# M215A.net
KiCad netlist of a schematic drawn in EAGLE
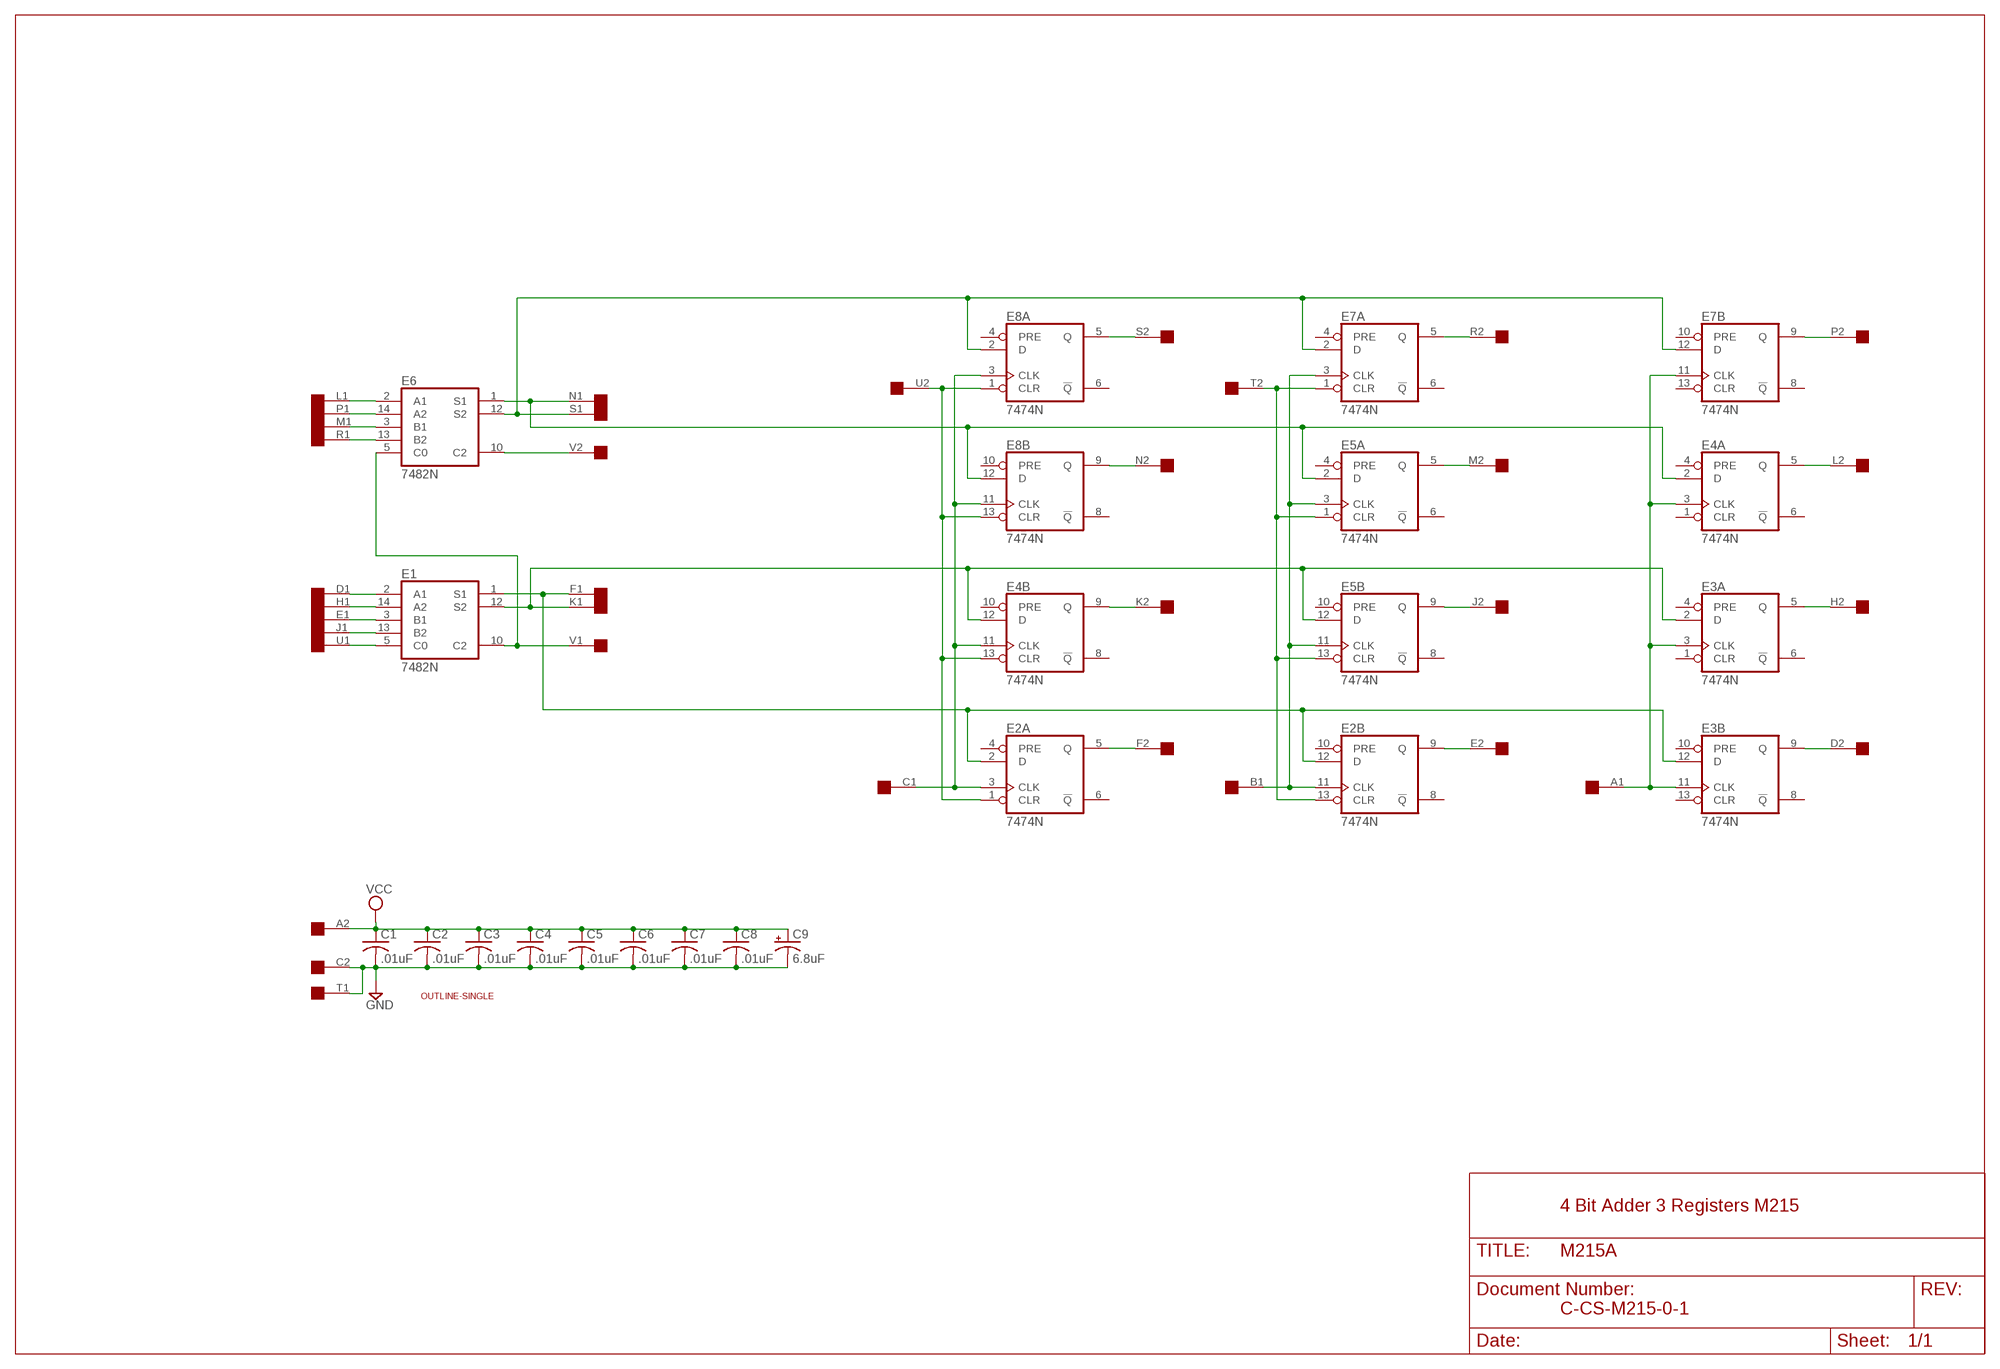
[diagram p0: schematic, sheet 1]

(export (version "E")
  (design (tool "Eeschema 10.0.6"))
  (components
    (comp (ref "C1")
      (value ".01uF")
      (footprint "eagle-import:C050-025X075")
      (libsource (lib "eagle-import") (part "C-US050-025X075"))
    )
    (comp (ref "C2")
      (value ".01uF")
      (footprint "eagle-import:C050-025X075")
      (libsource (lib "eagle-import") (part "C-US050-025X075"))
    )
    (comp (ref "C3")
      (value ".01uF")
      (footprint "eagle-import:C050-025X075")
      (libsource (lib "eagle-import") (part "C-US050-025X075"))
    )
    (comp (ref "C4")
      (value ".01uF")
      (footprint "eagle-import:C050-025X075")
      (libsource (lib "eagle-import") (part "C-US050-025X075"))
    )
    (comp (ref "C5")
      (value ".01uF")
      (footprint "eagle-import:C050-025X075")
      (libsource (lib "eagle-import") (part "C-US050-025X075"))
    )
    (comp (ref "C6")
      (value ".01uF")
      (footprint "eagle-import:C050-025X075")
      (libsource (lib "eagle-import") (part "C-US050-025X075"))
    )
    (comp (ref "C7")
      (value ".01uF")
      (footprint "eagle-import:C050-025X075")
      (libsource (lib "eagle-import") (part "C-US050-025X075"))
    )
    (comp (ref "C8")
      (value ".01uF")
      (footprint "eagle-import:C050-025X075")
      (libsource (lib "eagle-import") (part "C-US050-025X075"))
    )
    (comp (ref "C9")
      (value "6.8uF")
      (footprint "eagle-import:E12-8")
      (libsource (lib "eagle-import") (part "CPOL-USE20-8AXIAL"))
    )
    (comp (ref "E1")
      (value "7482N")
      (footprint "eagle-import:DIL14")
      (libsource (lib "eagle-import") (part "7482N"))
    )
    (comp (ref "E2")
      (value "7474N")
      (footprint "eagle-import:DIL14")
      (libsource (lib "eagle-import") (part "7474NS"))
    )
    (comp (ref "E3")
      (value "7474N")
      (footprint "eagle-import:DIL14")
      (libsource (lib "eagle-import") (part "7474NS"))
    )
    (comp (ref "E4")
      (value "7474N")
      (footprint "eagle-import:DIL14")
      (libsource (lib "eagle-import") (part "7474NS"))
    )
    (comp (ref "E5")
      (value "7474N")
      (footprint "eagle-import:DIL14")
      (libsource (lib "eagle-import") (part "7474NS"))
    )
    (comp (ref "E6")
      (value "7482N")
      (footprint "eagle-import:DIL14")
      (libsource (lib "eagle-import") (part "7482N"))
    )
    (comp (ref "E7")
      (value "7474N")
      (footprint "eagle-import:DIL14")
      (libsource (lib "eagle-import") (part "7474NS"))
    )
    (comp (ref "E8")
      (value "7474N")
      (footprint "eagle-import:DIL14")
      (libsource (lib "eagle-import") (part "7474NS"))
    )
    (comp (ref "U$1")
      (value "OUTLINE-SINGLE")
      (footprint "eagle-import:SINGLE")
      (libsource (lib "eagle-import") (part "OUTLINE-SINGLE"))
    )
    (comp (ref "U$2")
      (value "SINGLE")
      (footprint "eagle-import:EDGE-CON2")
      (libsource (lib "eagle-import") (part "SINGLE"))
    )
  )
  (nets
    (net (code "1") (name "GND") (class "Default")
      (node (ref "C1") (pin "2") (pinfunction "2_2") (pintype "passive"))
      (node (ref "C2") (pin "2") (pinfunction "2_2") (pintype "passive"))
      (node (ref "C3") (pin "2") (pinfunction "2_2") (pintype "passive"))
      (node (ref "C4") (pin "2") (pinfunction "2_2") (pintype "passive"))
      (node (ref "C5") (pin "2") (pinfunction "2_2") (pintype "passive"))
      (node (ref "C6") (pin "2") (pinfunction "2_2") (pintype "passive"))
      (node (ref "C7") (pin "2") (pinfunction "2_2") (pintype "passive"))
      (node (ref "C8") (pin "2") (pinfunction "2_2") (pintype "passive"))
      (node (ref "C9") (pin "-") (pinfunction "-_-") (pintype "passive"))
      (node (ref "U$2") (pin "C2") (pinfunction "1_C2") (pintype "bidirectional"))
      (node (ref "U$2") (pin "T1") (pinfunction "1_T1") (pintype "bidirectional"))
    )
    (net (code "2") (name "Net-(E1E-A1)") (class "Default")
      (node (ref "E1") (pin "2") (pinfunction "A1_2") (pintype "input"))
      (node (ref "U$2") (pin "D1") (pinfunction "1_D1") (pintype "bidirectional"))
    )
    (net (code "3") (name "Net-(E1E-A2)") (class "Default")
      (node (ref "E1") (pin "14") (pinfunction "A2_14") (pintype "input"))
      (node (ref "U$2") (pin "H1") (pinfunction "1_H1") (pintype "bidirectional"))
    )
    (net (code "4") (name "Net-(E1E-B1)") (class "Default")
      (node (ref "E1") (pin "3") (pinfunction "B1_3") (pintype "input"))
      (node (ref "U$2") (pin "E1") (pinfunction "1_E1") (pintype "bidirectional"))
    )
    (net (code "5") (name "Net-(E1E-B2)") (class "Default")
      (node (ref "E1") (pin "13") (pinfunction "B2_13") (pintype "input"))
      (node (ref "U$2") (pin "J1") (pinfunction "1_J1") (pintype "bidirectional"))
    )
    (net (code "6") (name "Net-(E1E-C0)") (class "Default")
      (node (ref "E1") (pin "5") (pinfunction "C0_5") (pintype "input"))
      (node (ref "U$2") (pin "U1") (pinfunction "1_U1") (pintype "bidirectional"))
    )
    (net (code "7") (name "Net-(E1E-C2)") (class "Default")
      (node (ref "E1") (pin "10") (pinfunction "C2_10") (pintype "output"))
      (node (ref "E6") (pin "5") (pinfunction "C0_5") (pintype "input"))
      (node (ref "U$2") (pin "V1") (pinfunction "1_V1") (pintype "bidirectional"))
    )
    (net (code "8") (name "Net-(E1E-S1)") (class "Default")
      (node (ref "E1") (pin "1") (pinfunction "S1_1") (pintype "output"))
      (node (ref "E2") (pin "12") (pinfunction "D_12") (pintype "input"))
      (node (ref "E2") (pin "2") (pinfunction "D_2") (pintype "input"))
      (node (ref "E3") (pin "12") (pinfunction "D_12") (pintype "input"))
      (node (ref "U$2") (pin "F1") (pinfunction "1_F1") (pintype "bidirectional"))
    )
    (net (code "9") (name "Net-(E1E-S2)") (class "Default")
      (node (ref "E1") (pin "12") (pinfunction "S2_12") (pintype "output"))
      (node (ref "E3") (pin "2") (pinfunction "D_2") (pintype "input"))
      (node (ref "E4") (pin "12") (pinfunction "D_12") (pintype "input"))
      (node (ref "E5") (pin "12") (pinfunction "D_12") (pintype "input"))
      (node (ref "U$2") (pin "K1") (pinfunction "1_K1") (pintype "bidirectional"))
    )
    (net (code "10") (name "Net-(E2A-CLK)") (class "Default")
      (node (ref "E2") (pin "3") (pinfunction "CLK_3") (pintype "input"))
      (node (ref "E4") (pin "11") (pinfunction "CLK_11") (pintype "input"))
      (node (ref "E8") (pin "11") (pinfunction "CLK_11") (pintype "input"))
      (node (ref "E8") (pin "3") (pinfunction "CLK_3") (pintype "input"))
      (node (ref "U$2") (pin "C1") (pinfunction "1_C1") (pintype "bidirectional"))
    )
    (net (code "11") (name "Net-(E2A-CLR)") (class "Default")
      (node (ref "E2") (pin "1") (pinfunction "CLR_1") (pintype "input"))
      (node (ref "E4") (pin "13") (pinfunction "CLR_13") (pintype "input"))
      (node (ref "E8") (pin "1") (pinfunction "CLR_1") (pintype "input"))
      (node (ref "E8") (pin "13") (pinfunction "CLR_13") (pintype "input"))
      (node (ref "U$2") (pin "U2") (pinfunction "1_U2") (pintype "bidirectional"))
    )
    (net (code "12") (name "Net-(E2A-Q)") (class "Default")
      (node (ref "E2") (pin "5") (pinfunction "Q_5") (pintype "output"))
      (node (ref "U$2") (pin "F2") (pinfunction "1_F2") (pintype "bidirectional"))
    )
    (net (code "13") (name "Net-(E2B-CLK)") (class "Default")
      (node (ref "E2") (pin "11") (pinfunction "CLK_11") (pintype "input"))
      (node (ref "E5") (pin "11") (pinfunction "CLK_11") (pintype "input"))
      (node (ref "E5") (pin "3") (pinfunction "CLK_3") (pintype "input"))
      (node (ref "E7") (pin "3") (pinfunction "CLK_3") (pintype "input"))
      (node (ref "U$2") (pin "B1") (pinfunction "1_B1") (pintype "bidirectional"))
    )
    (net (code "14") (name "Net-(E2B-CLR)") (class "Default")
      (node (ref "E2") (pin "13") (pinfunction "CLR_13") (pintype "input"))
      (node (ref "E5") (pin "1") (pinfunction "CLR_1") (pintype "input"))
      (node (ref "E5") (pin "13") (pinfunction "CLR_13") (pintype "input"))
      (node (ref "E7") (pin "1") (pinfunction "CLR_1") (pintype "input"))
      (node (ref "U$2") (pin "T2") (pinfunction "1_T2") (pintype "bidirectional"))
    )
    (net (code "15") (name "Net-(E2B-Q)") (class "Default")
      (node (ref "E2") (pin "9") (pinfunction "Q_9") (pintype "output"))
      (node (ref "U$2") (pin "E2") (pinfunction "1_E2") (pintype "bidirectional"))
    )
    (net (code "16") (name "Net-(E3A-CLK)") (class "Default")
      (node (ref "E3") (pin "11") (pinfunction "CLK_11") (pintype "input"))
      (node (ref "E3") (pin "3") (pinfunction "CLK_3") (pintype "input"))
      (node (ref "E4") (pin "3") (pinfunction "CLK_3") (pintype "input"))
      (node (ref "E7") (pin "11") (pinfunction "CLK_11") (pintype "input"))
      (node (ref "U$2") (pin "A1") (pinfunction "1_A1") (pintype "bidirectional"))
    )
    (net (code "17") (name "Net-(E3A-Q)") (class "Default")
      (node (ref "E3") (pin "5") (pinfunction "Q_5") (pintype "output"))
      (node (ref "U$2") (pin "H2") (pinfunction "1_H2") (pintype "bidirectional"))
    )
    (net (code "18") (name "Net-(E3B-Q)") (class "Default")
      (node (ref "E3") (pin "9") (pinfunction "Q_9") (pintype "output"))
      (node (ref "U$2") (pin "D2") (pinfunction "1_D2") (pintype "bidirectional"))
    )
    (net (code "19") (name "Net-(E4A-D)") (class "Default")
      (node (ref "E4") (pin "2") (pinfunction "D_2") (pintype "input"))
      (node (ref "E5") (pin "2") (pinfunction "D_2") (pintype "input"))
      (node (ref "E6") (pin "1") (pinfunction "S1_1") (pintype "output"))
      (node (ref "E8") (pin "12") (pinfunction "D_12") (pintype "input"))
      (node (ref "U$2") (pin "N1") (pinfunction "1_N1") (pintype "bidirectional"))
    )
    (net (code "20") (name "Net-(E4A-Q)") (class "Default")
      (node (ref "E4") (pin "5") (pinfunction "Q_5") (pintype "output"))
      (node (ref "U$2") (pin "L2") (pinfunction "1_L2") (pintype "bidirectional"))
    )
    (net (code "21") (name "Net-(E4B-Q)") (class "Default")
      (node (ref "E4") (pin "9") (pinfunction "Q_9") (pintype "output"))
      (node (ref "U$2") (pin "K2") (pinfunction "1_K2") (pintype "bidirectional"))
    )
    (net (code "22") (name "Net-(E5A-Q)") (class "Default")
      (node (ref "E5") (pin "5") (pinfunction "Q_5") (pintype "output"))
      (node (ref "U$2") (pin "M2") (pinfunction "1_M2") (pintype "bidirectional"))
    )
    (net (code "23") (name "Net-(E5B-Q)") (class "Default")
      (node (ref "E5") (pin "9") (pinfunction "Q_9") (pintype "output"))
      (node (ref "U$2") (pin "J2") (pinfunction "1_J2") (pintype "bidirectional"))
    )
    (net (code "24") (name "Net-(E6E-A1)") (class "Default")
      (node (ref "E6") (pin "2") (pinfunction "A1_2") (pintype "input"))
      (node (ref "U$2") (pin "L1") (pinfunction "1_L1") (pintype "bidirectional"))
    )
    (net (code "25") (name "Net-(E6E-A2)") (class "Default")
      (node (ref "E6") (pin "14") (pinfunction "A2_14") (pintype "input"))
      (node (ref "U$2") (pin "P1") (pinfunction "1_P1") (pintype "bidirectional"))
    )
    (net (code "26") (name "Net-(E6E-B1)") (class "Default")
      (node (ref "E6") (pin "3") (pinfunction "B1_3") (pintype "input"))
      (node (ref "U$2") (pin "M1") (pinfunction "1_M1") (pintype "bidirectional"))
    )
    (net (code "27") (name "Net-(E6E-B2)") (class "Default")
      (node (ref "E6") (pin "13") (pinfunction "B2_13") (pintype "input"))
      (node (ref "U$2") (pin "R1") (pinfunction "1_R1") (pintype "bidirectional"))
    )
    (net (code "28") (name "Net-(E6E-C2)") (class "Default")
      (node (ref "E6") (pin "10") (pinfunction "C2_10") (pintype "output"))
      (node (ref "U$2") (pin "V2") (pinfunction "1_V2") (pintype "bidirectional"))
    )
    (net (code "29") (name "Net-(E6E-S2)") (class "Default")
      (node (ref "E6") (pin "12") (pinfunction "S2_12") (pintype "output"))
      (node (ref "E7") (pin "12") (pinfunction "D_12") (pintype "input"))
      (node (ref "E7") (pin "2") (pinfunction "D_2") (pintype "input"))
      (node (ref "E8") (pin "2") (pinfunction "D_2") (pintype "input"))
      (node (ref "U$2") (pin "S1") (pinfunction "1_S1") (pintype "bidirectional"))
    )
    (net (code "30") (name "Net-(E7A-Q)") (class "Default")
      (node (ref "E7") (pin "5") (pinfunction "Q_5") (pintype "output"))
      (node (ref "U$2") (pin "R2") (pinfunction "1_R2") (pintype "bidirectional"))
    )
    (net (code "31") (name "Net-(E7B-Q)") (class "Default")
      (node (ref "E7") (pin "9") (pinfunction "Q_9") (pintype "output"))
      (node (ref "U$2") (pin "P2") (pinfunction "1_P2") (pintype "bidirectional"))
    )
    (net (code "32") (name "Net-(E8A-Q)") (class "Default")
      (node (ref "E8") (pin "5") (pinfunction "Q_5") (pintype "output"))
      (node (ref "U$2") (pin "S2") (pinfunction "1_S2") (pintype "bidirectional"))
    )
    (net (code "33") (name "Net-(E8B-Q)") (class "Default")
      (node (ref "E8") (pin "9") (pinfunction "Q_9") (pintype "output"))
      (node (ref "U$2") (pin "N2") (pinfunction "1_N2") (pintype "bidirectional"))
    )
    (net (code "34") (name "VCC") (class "Default")
      (node (ref "C1") (pin "1") (pinfunction "1_1") (pintype "passive"))
      (node (ref "C2") (pin "1") (pinfunction "1_1") (pintype "passive"))
      (node (ref "C3") (pin "1") (pinfunction "1_1") (pintype "passive"))
      (node (ref "C4") (pin "1") (pinfunction "1_1") (pintype "passive"))
      (node (ref "C5") (pin "1") (pinfunction "1_1") (pintype "passive"))
      (node (ref "C6") (pin "1") (pinfunction "1_1") (pintype "passive"))
      (node (ref "C7") (pin "1") (pinfunction "1_1") (pintype "passive"))
      (node (ref "C8") (pin "1") (pinfunction "1_1") (pintype "passive"))
      (node (ref "C9") (pin "+") (pinfunction "+_+") (pintype "passive"))
      (node (ref "U$2") (pin "A2") (pinfunction "1_A2") (pintype "bidirectional"))
    )
    (net (code "35") (name "unconnected-(E2A-PRE-Pad4)") (class "Default")
      (node (ref "E2") (pin "4") (pinfunction "PRE_4") (pintype "input"))
    )
    (net (code "36") (name "unconnected-(E2A-~{Q}-Pad6)") (class "Default")
      (node (ref "E2") (pin "6") (pinfunction "~{Q}_6") (pintype "output"))
    )
    (net (code "37") (name "unconnected-(E2B-PRE-Pad10)") (class "Default")
      (node (ref "E2") (pin "10") (pinfunction "PRE_10") (pintype "input"))
    )
    (net (code "38") (name "unconnected-(E2B-~{Q}-Pad8)") (class "Default")
      (node (ref "E2") (pin "8") (pinfunction "~{Q}_8") (pintype "output"))
    )
    (net (code "39") (name "unconnected-(E3A-CLR-Pad1)") (class "Default")
      (node (ref "E3") (pin "1") (pinfunction "CLR_1") (pintype "input"))
    )
    (net (code "40") (name "unconnected-(E3A-PRE-Pad4)") (class "Default")
      (node (ref "E3") (pin "4") (pinfunction "PRE_4") (pintype "input"))
    )
    (net (code "41") (name "unconnected-(E3A-~{Q}-Pad6)") (class "Default")
      (node (ref "E3") (pin "6") (pinfunction "~{Q}_6") (pintype "output"))
    )
    (net (code "42") (name "unconnected-(E3B-CLR-Pad13)") (class "Default")
      (node (ref "E3") (pin "13") (pinfunction "CLR_13") (pintype "input"))
    )
    (net (code "43") (name "unconnected-(E3B-PRE-Pad10)") (class "Default")
      (node (ref "E3") (pin "10") (pinfunction "PRE_10") (pintype "input"))
    )
    (net (code "44") (name "unconnected-(E3B-~{Q}-Pad8)") (class "Default")
      (node (ref "E3") (pin "8") (pinfunction "~{Q}_8") (pintype "output"))
    )
    (net (code "45") (name "unconnected-(E4A-CLR-Pad1)") (class "Default")
      (node (ref "E4") (pin "1") (pinfunction "CLR_1") (pintype "input"))
    )
    (net (code "46") (name "unconnected-(E4A-PRE-Pad4)") (class "Default")
      (node (ref "E4") (pin "4") (pinfunction "PRE_4") (pintype "input"))
    )
    (net (code "47") (name "unconnected-(E4A-~{Q}-Pad6)") (class "Default")
      (node (ref "E4") (pin "6") (pinfunction "~{Q}_6") (pintype "output"))
    )
    (net (code "48") (name "unconnected-(E4B-PRE-Pad10)") (class "Default")
      (node (ref "E4") (pin "10") (pinfunction "PRE_10") (pintype "input"))
    )
    (net (code "49") (name "unconnected-(E4B-~{Q}-Pad8)") (class "Default")
      (node (ref "E4") (pin "8") (pinfunction "~{Q}_8") (pintype "output"))
    )
    (net (code "50") (name "unconnected-(E5A-PRE-Pad4)") (class "Default")
      (node (ref "E5") (pin "4") (pinfunction "PRE_4") (pintype "input"))
    )
    (net (code "51") (name "unconnected-(E5A-~{Q}-Pad6)") (class "Default")
      (node (ref "E5") (pin "6") (pinfunction "~{Q}_6") (pintype "output"))
    )
    (net (code "52") (name "unconnected-(E5B-PRE-Pad10)") (class "Default")
      (node (ref "E5") (pin "10") (pinfunction "PRE_10") (pintype "input"))
    )
    (net (code "53") (name "unconnected-(E5B-~{Q}-Pad8)") (class "Default")
      (node (ref "E5") (pin "8") (pinfunction "~{Q}_8") (pintype "output"))
    )
    (net (code "54") (name "unconnected-(E7A-PRE-Pad4)") (class "Default")
      (node (ref "E7") (pin "4") (pinfunction "PRE_4") (pintype "input"))
    )
    (net (code "55") (name "unconnected-(E7A-~{Q}-Pad6)") (class "Default")
      (node (ref "E7") (pin "6") (pinfunction "~{Q}_6") (pintype "output"))
    )
    (net (code "56") (name "unconnected-(E7B-CLR-Pad13)") (class "Default")
      (node (ref "E7") (pin "13") (pinfunction "CLR_13") (pintype "input"))
    )
    (net (code "57") (name "unconnected-(E7B-PRE-Pad10)") (class "Default")
      (node (ref "E7") (pin "10") (pinfunction "PRE_10") (pintype "input"))
    )
    (net (code "58") (name "unconnected-(E7B-~{Q}-Pad8)") (class "Default")
      (node (ref "E7") (pin "8") (pinfunction "~{Q}_8") (pintype "output"))
    )
    (net (code "59") (name "unconnected-(E8A-PRE-Pad4)") (class "Default")
      (node (ref "E8") (pin "4") (pinfunction "PRE_4") (pintype "input"))
    )
    (net (code "60") (name "unconnected-(E8A-~{Q}-Pad6)") (class "Default")
      (node (ref "E8") (pin "6") (pinfunction "~{Q}_6") (pintype "output"))
    )
    (net (code "61") (name "unconnected-(E8B-PRE-Pad10)") (class "Default")
      (node (ref "E8") (pin "10") (pinfunction "PRE_10") (pintype "input"))
    )
    (net (code "62") (name "unconnected-(E8B-~{Q}-Pad8)") (class "Default")
      (node (ref "E8") (pin "8") (pinfunction "~{Q}_8") (pintype "output"))
    )
  )
)
